# AUDIO_AMP_NB2B.net
KiCad netlist of a schematic drawn in Altium Designer
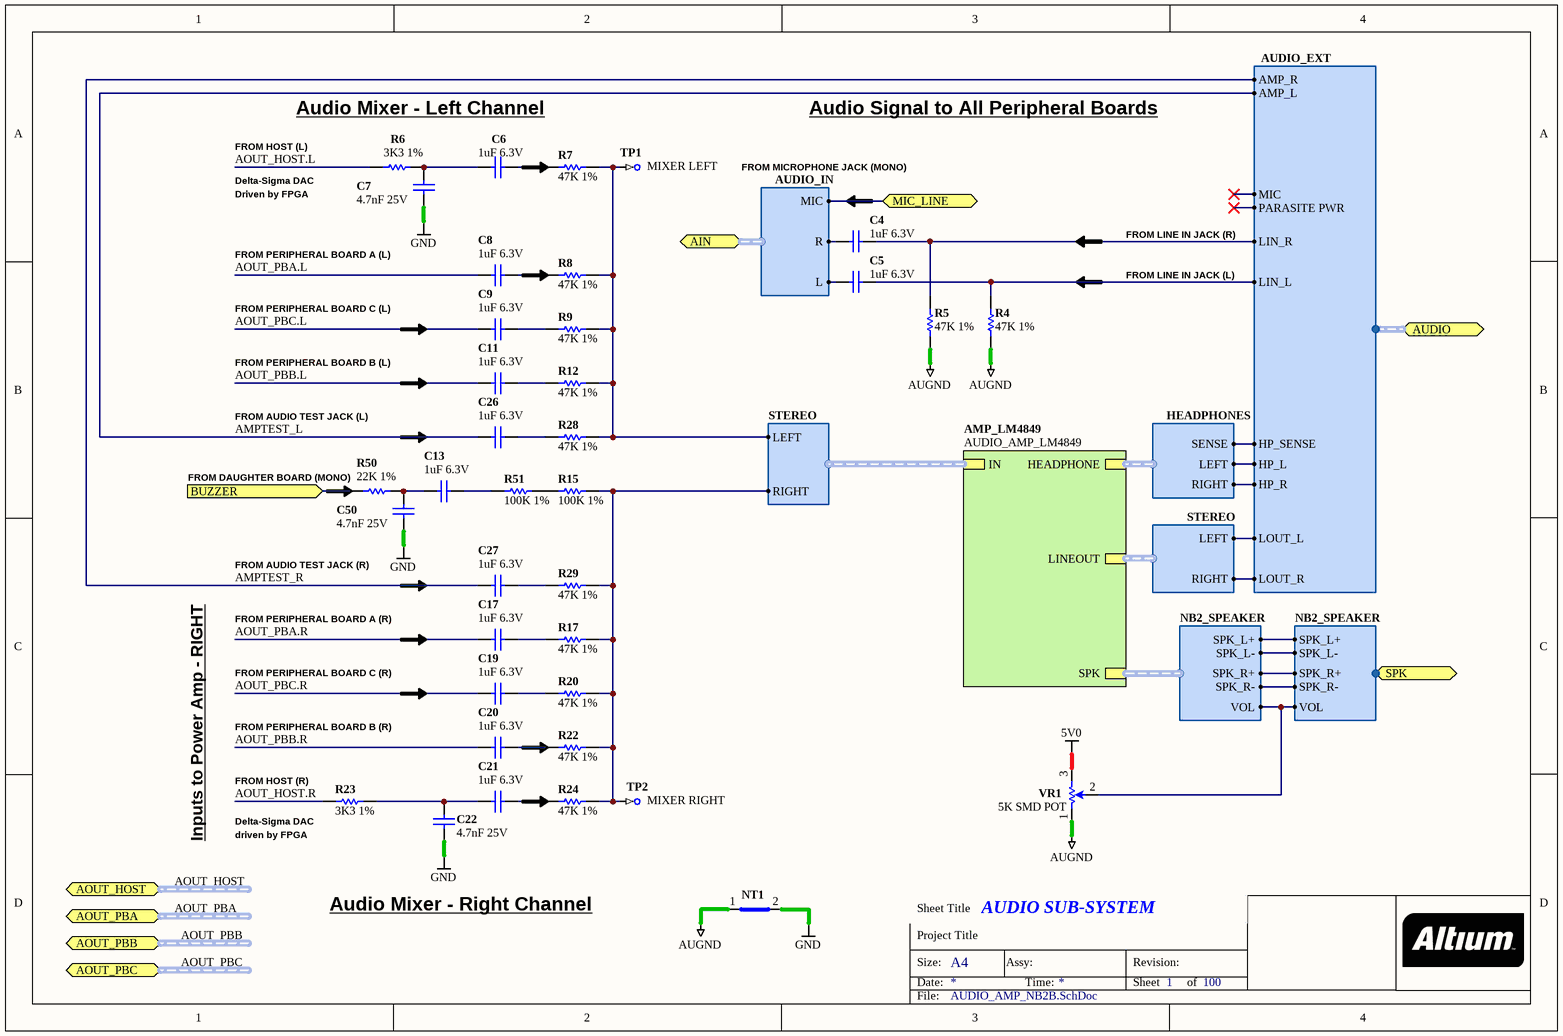
[diagram p0: AUDIO_AMP_NB2B.SchDoc]

(export (version "E")
  (design (tool "Eeschema 10.0.6"))
  (components
    (comp (ref "C4")
      (value "1uF 6.3V")
      (footprint "CAPC1005-STAR")
      (description "Capacitor, Ceramic, 1uF 10% 6.3V 0402 (1005) X5R")
      (fields (field (name "TOLERANCE") "10 %"))
      (libsource (lib "altium-import") (part "root_3_CAP-NP_"))
    )
    (comp (ref "C5")
      (value "1uF 6.3V")
      (footprint "CAPC1005-STAR")
      (description "Capacitor, Ceramic, 1uF 10% 6.3V 0402 (1005) X5R")
      (fields (field (name "TOLERANCE") "10 %"))
      (libsource (lib "altium-import") (part "root_3_CAP-NP_"))
    )
    (comp (ref "C6")
      (value "1uF 6.3V")
      (footprint "CAPC1005-STAR")
      (description "Capacitor, Ceramic, 1uF 10% 6.3V 0402 (1005) X5R")
      (fields (field (name "TOLERANCE") "10 %"))
      (libsource (lib "altium-import") (part "root_3_CAP-NP_"))
    )
    (comp (ref "C7")
      (value "4.7nF 25V")
      (footprint "CAPC1005-STAR")
      (description "Capacitor, Ceramic, 4.7nF 10% 25V 0402 (1005) X7R")
      (fields (field (name "TOLERANCE") "10 %"))
      (libsource (lib "altium-import") (part "root_0_CAP-NP_"))
    )
    (comp (ref "C8")
      (value "1uF 6.3V")
      (footprint "CAPC1005-STAR")
      (description "Capacitor, Ceramic, 1uF 10% 6.3V 0402 (1005) X5R")
      (fields (field (name "TOLERANCE") "10 %"))
      (libsource (lib "altium-import") (part "root_3_CAP-NP_"))
    )
    (comp (ref "C9")
      (value "1uF 6.3V")
      (footprint "CAPC1005-STAR")
      (description "Capacitor, Ceramic, 1uF 10% 6.3V 0402 (1005) X5R")
      (fields (field (name "TOLERANCE") "10 %"))
      (libsource (lib "altium-import") (part "root_3_CAP-NP_"))
    )
    (comp (ref "C11")
      (value "1uF 6.3V")
      (footprint "CAPC1005-STAR")
      (description "Capacitor, Ceramic, 1uF 10% 6.3V 0402 (1005) X5R")
      (fields (field (name "TOLERANCE") "10 %"))
      (libsource (lib "altium-import") (part "root_3_CAP-NP_"))
    )
    (comp (ref "C13")
      (value "1uF 6.3V")
      (footprint "CAPC1005-STAR")
      (description "Capacitor, Ceramic, 1uF 10% 6.3V 0402 (1005) X5R")
      (fields (field (name "TOLERANCE") "10 %"))
      (libsource (lib "altium-import") (part "root_3_CAP-NP_"))
    )
    (comp (ref "C17")
      (value "1uF 6.3V")
      (footprint "CAPC1005-STAR")
      (description "Capacitor, Ceramic, 1uF 10% 6.3V 0402 (1005) X5R")
      (fields (field (name "TOLERANCE") "10 %"))
      (libsource (lib "altium-import") (part "root_3_CAP-NP_"))
    )
    (comp (ref "C19")
      (value "1uF 6.3V")
      (footprint "CAPC1005-STAR")
      (description "Capacitor, Ceramic, 1uF 10% 6.3V 0402 (1005) X5R")
      (fields (field (name "TOLERANCE") "10 %"))
      (libsource (lib "altium-import") (part "root_3_CAP-NP_"))
    )
    (comp (ref "C20")
      (value "1uF 6.3V")
      (footprint "CAPC1005-STAR")
      (description "Capacitor, Ceramic, 1uF 10% 6.3V 0402 (1005) X5R")
      (fields (field (name "TOLERANCE") "10 %"))
      (libsource (lib "altium-import") (part "root_3_CAP-NP_"))
    )
    (comp (ref "C21")
      (value "1uF 6.3V")
      (footprint "CAPC1005-STAR")
      (description "Capacitor, Ceramic, 1uF 10% 6.3V 0402 (1005) X5R")
      (fields (field (name "TOLERANCE") "10 %"))
      (libsource (lib "altium-import") (part "root_3_CAP-NP_"))
    )
    (comp (ref "C22")
      (value "4.7nF 25V")
      (footprint "CAPC1005-STAR")
      (description "Capacitor, Ceramic, 4.7nF 10% 25V 0402 (1005) X7R")
      (fields (field (name "TOLERANCE") "10 %"))
      (libsource (lib "altium-import") (part "root_0_CAP-NP_"))
    )
    (comp (ref "C26")
      (value "1uF 6.3V")
      (footprint "CAPC1005-STAR")
      (description "Capacitor, Ceramic, 1uF 10% 6.3V 0402 (1005) X5R")
      (fields (field (name "TOLERANCE") "10 %"))
      (libsource (lib "altium-import") (part "root_3_CAP-NP_"))
    )
    (comp (ref "C27")
      (value "1uF 6.3V")
      (footprint "CAPC1005-STAR")
      (description "Capacitor, Ceramic, 1uF 10% 6.3V 0402 (1005) X5R")
      (fields (field (name "TOLERANCE") "10 %"))
      (libsource (lib "altium-import") (part "root_3_CAP-NP_"))
    )
    (comp (ref "C50")
      (value "4.7nF 25V")
      (footprint "CAPC1005-STAR")
      (description "Capacitor, Ceramic, 4.7nF 10% 25V 0402 (1005) X7R")
      (fields (field (name "TOLERANCE") "10 %"))
      (libsource (lib "altium-import") (part "root_0_CAP-NP_"))
    )
    (comp (ref "NT1")
      (value "Net Tie SMT2")
      (footprint "NETTIE-SMT2-31X39")
      (description "Net-Tie, Surface Mount, 2 x 2.0mm x 0.8mm SMT Pads - For 0.8mm Track")
      (libsource (lib "AltiumDesignLibrary") (part "NETTIE-SMT2"))
    )
    (comp (ref "R4")
      (value "47K 1%")
      (footprint "RESC1005-STAR")
      (description "Resistor, 47K 1% 0402 (1005)")
      (fields (field (name "TOLERANCE") "1 %"))
      (libsource (lib "altium-import") (part "root_2_RES_"))
    )
    (comp (ref "R5")
      (value "47K 1%")
      (footprint "RESC1005-STAR")
      (description "Resistor, 47K 1% 0402 (1005)")
      (fields (field (name "TOLERANCE") "1 %"))
      (libsource (lib "altium-import") (part "root_2_RES_"))
    )
    (comp (ref "R6")
      (value "3K3 1%")
      (footprint "RESC1005-STAR")
      (description "Resistor, 3K3 1% 0402 (1005)")
      (fields (field (name "TOLERANCE") "1 %"))
      (libsource (lib "altium-import") (part "root_1_RES_"))
    )
    (comp (ref "R7")
      (value "47K 1%")
      (footprint "RESC1005-STAR")
      (description "Resistor, 47K 1% 0402 (1005)")
      (fields (field (name "TOLERANCE") "1 %"))
      (libsource (lib "altium-import") (part "root_1_RES_"))
    )
    (comp (ref "R8")
      (value "47K 1%")
      (footprint "RESC1005-STAR")
      (description "Resistor, 47K 1% 0402 (1005)")
      (fields (field (name "TOLERANCE") "1 %"))
      (libsource (lib "altium-import") (part "root_1_RES_"))
    )
    (comp (ref "R9")
      (value "47K 1%")
      (footprint "RESC1005-STAR")
      (description "Resistor, 47K 1% 0402 (1005)")
      (fields (field (name "TOLERANCE") "1 %"))
      (libsource (lib "altium-import") (part "root_1_RES_"))
    )
    (comp (ref "R12")
      (value "47K 1%")
      (footprint "RESC1005-STAR")
      (description "Resistor, 47K 1% 0402 (1005)")
      (fields (field (name "TOLERANCE") "1 %"))
      (libsource (lib "altium-import") (part "root_1_RES_"))
    )
    (comp (ref "R15")
      (value "100K 1%")
      (footprint "RESC1005-STAR")
      (description "Resistor, 100K 1% 0402 (1005)")
      (fields (field (name "TOLERANCE") "1 %"))
      (libsource (lib "altium-import") (part "root_1_RES_"))
    )
    (comp (ref "R17")
      (value "47K 1%")
      (footprint "RESC1005-STAR")
      (description "Resistor, 47K 1% 0402 (1005)")
      (fields (field (name "TOLERANCE") "1 %"))
      (libsource (lib "altium-import") (part "root_1_RES_"))
    )
    (comp (ref "R20")
      (value "47K 1%")
      (footprint "RESC1005-STAR")
      (description "Resistor, 47K 1% 0402 (1005)")
      (fields (field (name "TOLERANCE") "1 %"))
      (libsource (lib "altium-import") (part "root_1_RES_"))
    )
    (comp (ref "R22")
      (value "47K 1%")
      (footprint "RESC1005-STAR")
      (description "Resistor, 47K 1% 0402 (1005)")
      (fields (field (name "TOLERANCE") "1 %"))
      (libsource (lib "altium-import") (part "root_1_RES_"))
    )
    (comp (ref "R23")
      (value "3K3 1%")
      (footprint "RESC1005-STAR")
      (description "Resistor, 3K3 1% 0402 (1005)")
      (fields (field (name "TOLERANCE") "1 %"))
      (libsource (lib "altium-import") (part "root_1_RES_"))
    )
    (comp (ref "R24")
      (value "47K 1%")
      (footprint "RESC1005-STAR")
      (description "Resistor, 47K 1% 0402 (1005)")
      (fields (field (name "TOLERANCE") "1 %"))
      (libsource (lib "altium-import") (part "root_1_RES_"))
    )
    (comp (ref "R28")
      (value "47K 1%")
      (footprint "RESC1005-STAR")
      (description "Resistor, 47K 1% 0402 (1005)")
      (fields (field (name "TOLERANCE") "1 %"))
      (libsource (lib "altium-import") (part "root_1_RES_"))
    )
    (comp (ref "R29")
      (value "47K 1%")
      (footprint "RESC1005-STAR")
      (description "Resistor, 47K 1% 0402 (1005)")
      (fields (field (name "TOLERANCE") "1 %"))
      (libsource (lib "altium-import") (part "root_1_RES_"))
    )
    (comp (ref "R50")
      (value "22K 1%")
      (footprint "RESC1005-STAR")
      (description "Resistor, 22K 1% 0402 (1005)")
      (fields (field (name "TOLERANCE") "1 %"))
      (libsource (lib "altium-import") (part "root_1_RES_"))
    )
    (comp (ref "R51")
      (value "100K 1%")
      (footprint "RESC1005-STAR")
      (description "Resistor, 100K 1% 0402 (1005)")
      (fields (field (name "TOLERANCE") "1 %"))
      (libsource (lib "altium-import") (part "root_1_RES_"))
    )
    (comp (ref "TP1")
      (value "MIXER LEFT")
      (footprint "TestPin")
      (description "Test Point, PCB Mount with Silkscreen Box")
      (libsource (lib "AltiumDesignLibrary") (part "TestPin"))
    )
    (comp (ref "TP2")
      (value "MIXER RIGHT")
      (footprint "TestPin")
      (description "Test Point, PCB Mount with Silkscreen Box")
      (libsource (lib "AltiumDesignLibrary") (part "TestPin"))
    )
    (comp (ref "VR1")
      (value "5K SMD POT")
      (footprint "TRIMMER_3361")
      (description "Potentiometer, SMD, 3361 Side Entry, Single Turn")
      (libsource (lib "AltiumDesignLibrary") (part "POT"))
    )
  )
  (nets
    (net (code "10") (name "/AMPTEST_L") (class "Default")
      (node (ref "C26") (pin "2") (pinfunction "2_2") (pintype "passive"))
    )
    (net (code "11") (name "/AMPTEST_R") (class "Default")
      (node (ref "C27") (pin "2") (pinfunction "2_2") (pintype "passive"))
    )
    (net (code "12") (name "/AOUT_HOST.L") (class "Default")
      (node (ref "R6") (pin "1") (pinfunction "1_1") (pintype "passive"))
    )
    (net (code "13") (name "/AOUT_HOST.R") (class "Default")
      (node (ref "R23") (pin "1") (pinfunction "1_1") (pintype "passive"))
    )
    (net (code "14") (name "/AOUT_PBA.L") (class "Default")
      (node (ref "C8") (pin "2") (pinfunction "2_2") (pintype "passive"))
    )
    (net (code "15") (name "/AOUT_PBA.R") (class "Default")
      (node (ref "C17") (pin "2") (pinfunction "2_2") (pintype "passive"))
    )
    (net (code "16") (name "/AOUT_PBB.L") (class "Default")
      (node (ref "C11") (pin "2") (pinfunction "2_2") (pintype "passive"))
    )
    (net (code "17") (name "/AOUT_PBB.R") (class "Default")
      (node (ref "C20") (pin "2") (pinfunction "2_2") (pintype "passive"))
    )
    (net (code "18") (name "/AOUT_PBC.L") (class "Default")
      (node (ref "C9") (pin "2") (pinfunction "2_2") (pintype "passive"))
    )
    (net (code "19") (name "/AOUT_PBC.R") (class "Default")
      (node (ref "C19") (pin "2") (pinfunction "2_2") (pintype "passive"))
    )
    (net (code "20") (name "/BUZZER") (class "Default")
      (node (ref "R50") (pin "1") (pinfunction "1_1") (pintype "passive"))
    )
    (net (code "24") (name "/L") (class "Default")
      (node (ref "C5") (pin "2") (pinfunction "2_2") (pintype "passive"))
    )
    (net (code "25") (name "/LIN_L") (class "Default")
      (node (ref "C5") (pin "1") (pinfunction "1_1") (pintype "passive"))
      (node (ref "R4") (pin "2") (pinfunction "2_2") (pintype "passive"))
    )
    (net (code "26") (name "/LIN_R") (class "Default")
      (node (ref "C4") (pin "1") (pinfunction "1_1") (pintype "passive"))
      (node (ref "R5") (pin "2") (pinfunction "2_2") (pintype "passive"))
    )
    (net (code "31") (name "/R") (class "Default")
      (node (ref "C4") (pin "2") (pinfunction "2_2") (pintype "passive"))
    )
    (net (code "36") (name "/VOL") (class "Default")
      (node (ref "VR1") (pin "2") (pinfunction "2_2") (pintype "passive"))
    )
    (net (code "46") (name "5V0") (class "Default")
      (node (ref "VR1") (pin "3") (pinfunction "3_3") (pintype "passive"))
    )
    (net (code "47") (name "AUGND") (class "Default")
      (node (ref "NT1") (pin "1") (pinfunction "Net1_1") (pintype "passive"))
      (node (ref "R4") (pin "1") (pinfunction "1_1") (pintype "passive"))
      (node (ref "R5") (pin "1") (pinfunction "1_1") (pintype "passive"))
      (node (ref "VR1") (pin "1") (pinfunction "1_1") (pintype "passive"))
    )
    (net (code "48") (name "GND") (class "Default")
      (node (ref "C22") (pin "2") (pinfunction "2_2") (pintype "passive"))
      (node (ref "C50") (pin "2") (pinfunction "2_2") (pintype "passive"))
      (node (ref "C7") (pin "2") (pinfunction "2_2") (pintype "passive"))
      (node (ref "NT1") (pin "2") (pinfunction "Net2_2") (pintype "passive"))
    )
    (net (code "49") (name "Net-(C6-Pad1)") (class "Default")
      (node (ref "C6") (pin "1") (pinfunction "1_1") (pintype "passive"))
      (node (ref "R7") (pin "1") (pinfunction "1_1") (pintype "passive"))
    )
    (net (code "50") (name "Net-(C6-Pad2)") (class "Default")
      (node (ref "C6") (pin "2") (pinfunction "2_2") (pintype "passive"))
      (node (ref "C7") (pin "1") (pinfunction "1_1") (pintype "passive"))
      (node (ref "R6") (pin "2") (pinfunction "2_2") (pintype "passive"))
    )
    (net (code "51") (name "Net-(C8-Pad1)") (class "Default")
      (node (ref "C8") (pin "1") (pinfunction "1_1") (pintype "passive"))
      (node (ref "R8") (pin "1") (pinfunction "1_1") (pintype "passive"))
    )
    (net (code "52") (name "Net-(C9-Pad1)") (class "Default")
      (node (ref "C9") (pin "1") (pinfunction "1_1") (pintype "passive"))
      (node (ref "R9") (pin "1") (pinfunction "1_1") (pintype "passive"))
    )
    (net (code "53") (name "Net-(C11-Pad1)") (class "Default")
      (node (ref "C11") (pin "1") (pinfunction "1_1") (pintype "passive"))
      (node (ref "R12") (pin "1") (pinfunction "1_1") (pintype "passive"))
    )
    (net (code "54") (name "Net-(C13-Pad1)") (class "Default")
      (node (ref "C13") (pin "1") (pinfunction "1_1") (pintype "passive"))
      (node (ref "R51") (pin "1") (pinfunction "1_1") (pintype "passive"))
    )
    (net (code "55") (name "Net-(C13-Pad2)") (class "Default")
      (node (ref "C13") (pin "2") (pinfunction "2_2") (pintype "passive"))
      (node (ref "C50") (pin "1") (pinfunction "1_1") (pintype "passive"))
      (node (ref "R50") (pin "2") (pinfunction "2_2") (pintype "passive"))
    )
    (net (code "56") (name "Net-(C17-Pad1)") (class "Default")
      (node (ref "C17") (pin "1") (pinfunction "1_1") (pintype "passive"))
      (node (ref "R17") (pin "1") (pinfunction "1_1") (pintype "passive"))
    )
    (net (code "57") (name "Net-(C19-Pad1)") (class "Default")
      (node (ref "C19") (pin "1") (pinfunction "1_1") (pintype "passive"))
      (node (ref "R20") (pin "1") (pinfunction "1_1") (pintype "passive"))
    )
    (net (code "58") (name "Net-(C20-Pad1)") (class "Default")
      (node (ref "C20") (pin "1") (pinfunction "1_1") (pintype "passive"))
      (node (ref "R22") (pin "1") (pinfunction "1_1") (pintype "passive"))
    )
    (net (code "59") (name "Net-(C21-Pad1)") (class "Default")
      (node (ref "C21") (pin "1") (pinfunction "1_1") (pintype "passive"))
      (node (ref "R24") (pin "1") (pinfunction "1_1") (pintype "passive"))
    )
    (net (code "60") (name "Net-(C21-Pad2)") (class "Default")
      (node (ref "C21") (pin "2") (pinfunction "2_2") (pintype "passive"))
      (node (ref "C22") (pin "1") (pinfunction "1_1") (pintype "passive"))
      (node (ref "R23") (pin "2") (pinfunction "2_2") (pintype "passive"))
    )
    (net (code "61") (name "Net-(C26-Pad1)") (class "Default")
      (node (ref "C26") (pin "1") (pinfunction "1_1") (pintype "passive"))
      (node (ref "R28") (pin "1") (pinfunction "1_1") (pintype "passive"))
    )
    (net (code "62") (name "Net-(C27-Pad1)") (class "Default")
      (node (ref "C27") (pin "1") (pinfunction "1_1") (pintype "passive"))
      (node (ref "R29") (pin "1") (pinfunction "1_1") (pintype "passive"))
    )
    (net (code "63") (name "Net-(R12-Pad2)") (class "Default")
      (node (ref "R12") (pin "2") (pinfunction "2_2") (pintype "passive"))
      (node (ref "R28") (pin "2") (pinfunction "2_2") (pintype "passive"))
      (node (ref "R7") (pin "2") (pinfunction "2_2") (pintype "passive"))
      (node (ref "R8") (pin "2") (pinfunction "2_2") (pintype "passive"))
      (node (ref "R9") (pin "2") (pinfunction "2_2") (pintype "passive"))
      (node (ref "TP1") (pin "1") (pinfunction "1_1") (pintype "input"))
    )
    (net (code "64") (name "Net-(R15-Pad1)") (class "Default")
      (node (ref "R15") (pin "1") (pinfunction "1_1") (pintype "passive"))
      (node (ref "R51") (pin "2") (pinfunction "2_2") (pintype "passive"))
    )
    (net (code "65") (name "Net-(R15-Pad2)") (class "Default")
      (node (ref "R15") (pin "2") (pinfunction "2_2") (pintype "passive"))
      (node (ref "R17") (pin "2") (pinfunction "2_2") (pintype "passive"))
      (node (ref "R20") (pin "2") (pinfunction "2_2") (pintype "passive"))
      (node (ref "R22") (pin "2") (pinfunction "2_2") (pintype "passive"))
      (node (ref "R24") (pin "2") (pinfunction "2_2") (pintype "passive"))
      (node (ref "R29") (pin "2") (pinfunction "2_2") (pintype "passive"))
      (node (ref "TP2") (pin "1") (pinfunction "1_1") (pintype "input"))
    )
  )
)
